# Puzzle_Serial_Bluetooth_v0_9b.net
KiCad netlist of a schematic drawn in EAGLE
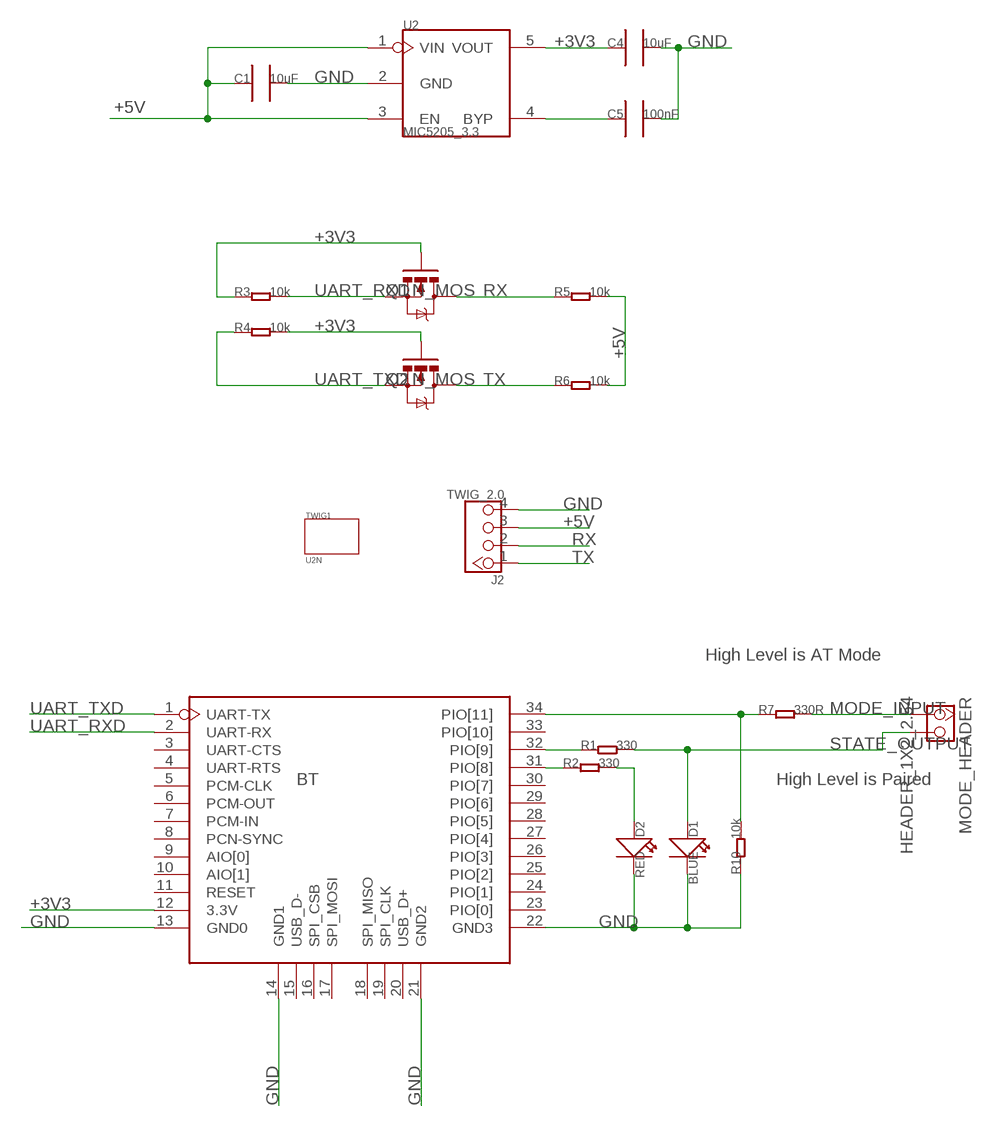
[diagram p0: schematic, sheet 1]

(export (version "E")
  (design (tool "Eeschema 10.0.6"))
  (components
    (comp (ref "BT")
      (value "SERIAL_BLUETEETHSMT")
      (footprint "eagle-import:SERIAL_BLUETEETH")
      (libsource (lib "eagle-import") (part "SERIAL_BLUETEETHSMT"))
    )
    (comp (ref "C1")
      (value "10uF")
      (footprint "eagle-import:0805_S")
      (libsource (lib "eagle-import") (part "C0805_S"))
    )
    (comp (ref "C4")
      (value "10uF")
      (footprint "eagle-import:0805_S")
      (libsource (lib "eagle-import") (part "C0805_S"))
    )
    (comp (ref "C5")
      (value "100nF")
      (footprint "eagle-import:0603_S")
      (libsource (lib "eagle-import") (part "C0603_S"))
    )
    (comp (ref "D1")
      (value "BLUE")
      (footprint "eagle-import:LED0603")
      (libsource (lib "eagle-import") (part "LED0603_DD"))
    )
    (comp (ref "D2")
      (value "RED")
      (footprint "eagle-import:LED0603")
      (libsource (lib "eagle-import") (part "LED0603_DD"))
    )
    (comp (ref "J2")
      (value "TWIG_2.0")
      (footprint "eagle-import:2.0_1X4")
      (libsource (lib "eagle-import") (part "TWIG_2.0"))
    )
    (comp (ref "MODE_HEADER")
      (value "HEADER_1X2_2.54")
      (footprint "eagle-import:CK_1_2")
      (libsource (lib "eagle-import") (part "HEADER_1X2_2.54"))
    )
    (comp (ref "Q1")
      (value "N_MOS")
      (footprint "eagle-import:SOT23")
      (libsource (lib "eagle-import") (part "N_MOS"))
    )
    (comp (ref "Q2")
      (value "N_MOS")
      (footprint "eagle-import:SOT23")
      (libsource (lib "eagle-import") (part "N_MOS"))
    )
    (comp (ref "R1")
      (value "330")
      (footprint "eagle-import:0603")
      (libsource (lib "eagle-import") (part "R0603"))
    )
    (comp (ref "R2")
      (value "330")
      (footprint "eagle-import:0603")
      (libsource (lib "eagle-import") (part "R0603"))
    )
    (comp (ref "R3")
      (value "10k")
      (footprint "eagle-import:0603_S")
      (libsource (lib "eagle-import") (part "R0603_S"))
    )
    (comp (ref "R4")
      (value "10k")
      (footprint "eagle-import:0603_S")
      (libsource (lib "eagle-import") (part "R0603_S"))
    )
    (comp (ref "R5")
      (value "10k")
      (footprint "eagle-import:0603_S")
      (libsource (lib "eagle-import") (part "R0603_S"))
    )
    (comp (ref "R6")
      (value "10k")
      (footprint "eagle-import:0603_S")
      (libsource (lib "eagle-import") (part "R0603_S"))
    )
    (comp (ref "R7")
      (value "330R")
      (footprint "eagle-import:0603_S")
      (libsource (lib "eagle-import") (part "R0603_S"))
    )
    (comp (ref "R10")
      (value "10k")
      (footprint "eagle-import:0603_S")
      (libsource (lib "eagle-import") (part "R0603_S"))
    )
    (comp (ref "TWIG1")
      (value "U2N")
      (footprint "eagle-import:U2N")
      (libsource (lib "eagle-import") (part "U2N"))
    )
    (comp (ref "U2")
      (value "MIC5205_3.3")
      (footprint "eagle-import:SOT23-5")
      (libsource (lib "eagle-import") (part "MIC5025_X.X"))
    )
  )
  (nets
    (net (code "1") (name "/+3V3") (class "Default")
      (node (ref "BT") (pin "12") (pinfunction "3.3V_12") (pintype "bidirectional"))
      (node (ref "C4") (pin "1") (pinfunction "1_1") (pintype "bidirectional"))
      (node (ref "Q1") (pin "1") (pinfunction "G_1") (pintype "passive"))
      (node (ref "Q2") (pin "1") (pinfunction "G_1") (pintype "passive"))
      (node (ref "R3") (pin "1") (pinfunction "1_1") (pintype "bidirectional"))
      (node (ref "R4") (pin "2") (pinfunction "2_2") (pintype "bidirectional"))
      (node (ref "U2") (pin "5") (pinfunction "VOUT_5") (pintype "bidirectional"))
    )
    (net (code "2") (name "/+5V") (class "Default")
      (node (ref "C1") (pin "1") (pinfunction "1_1") (pintype "bidirectional"))
      (node (ref "J2") (pin "3") (pinfunction "3_3") (pintype "bidirectional"))
      (node (ref "R5") (pin "2") (pinfunction "2_2") (pintype "bidirectional"))
      (node (ref "R6") (pin "2") (pinfunction "2_2") (pintype "bidirectional"))
      (node (ref "U2") (pin "1") (pinfunction "VIN_1") (pintype "bidirectional"))
      (node (ref "U2") (pin "3") (pinfunction "EN_3") (pintype "bidirectional"))
    )
    (net (code "3") (name "/GND") (class "Default")
      (node (ref "BT") (pin "13") (pinfunction "GND0_13") (pintype "bidirectional"))
      (node (ref "BT") (pin "14") (pinfunction "GND1_14") (pintype "bidirectional"))
      (node (ref "BT") (pin "21") (pinfunction "GND2_21") (pintype "bidirectional"))
      (node (ref "BT") (pin "22") (pinfunction "GND3_22") (pintype "bidirectional"))
      (node (ref "C1") (pin "2") (pinfunction "2_2") (pintype "bidirectional"))
      (node (ref "C4") (pin "2") (pinfunction "2_2") (pintype "bidirectional"))
      (node (ref "C5") (pin "2") (pinfunction "2_2") (pintype "bidirectional"))
      (node (ref "D1") (pin "2") (pinfunction "-_2") (pintype "bidirectional"))
      (node (ref "D2") (pin "2") (pinfunction "-_2") (pintype "bidirectional"))
      (node (ref "J2") (pin "4") (pinfunction "4_4") (pintype "bidirectional"))
      (node (ref "R10") (pin "1") (pinfunction "1_1") (pintype "bidirectional"))
      (node (ref "U2") (pin "2") (pinfunction "GND_2") (pintype "bidirectional"))
    )
    (net (code "4") (name "/MODE_INPUT") (class "Default")
      (node (ref "MODE_HEADER") (pin "1") (pinfunction "1_1") (pintype "bidirectional"))
      (node (ref "R7") (pin "2") (pinfunction "2_2") (pintype "bidirectional"))
    )
    (net (code "5") (name "/RX") (class "Default")
      (node (ref "J2") (pin "2") (pinfunction "2_2") (pintype "bidirectional"))
      (node (ref "Q1") (pin "3") (pinfunction "D_3") (pintype "passive"))
      (node (ref "R5") (pin "1") (pinfunction "1_1") (pintype "bidirectional"))
    )
    (net (code "6") (name "/STATE_OUTPUT") (class "Default")
      (node (ref "D1") (pin "1") (pinfunction "+_1") (pintype "bidirectional"))
      (node (ref "MODE_HEADER") (pin "2") (pinfunction "2_2") (pintype "bidirectional"))
      (node (ref "R1") (pin "2") (pinfunction "2_2") (pintype "bidirectional"))
    )
    (net (code "7") (name "/TX") (class "Default")
      (node (ref "J2") (pin "1") (pinfunction "1_1") (pintype "bidirectional"))
      (node (ref "Q2") (pin "3") (pinfunction "D_3") (pintype "passive"))
      (node (ref "R6") (pin "1") (pinfunction "1_1") (pintype "bidirectional"))
    )
    (net (code "8") (name "/UART_RXD") (class "Default")
      (node (ref "BT") (pin "2") (pinfunction "UART-RX_2") (pintype "bidirectional"))
      (node (ref "Q1") (pin "2") (pinfunction "S_2") (pintype "passive"))
      (node (ref "R3") (pin "2") (pinfunction "2_2") (pintype "bidirectional"))
    )
    (net (code "9") (name "/UART_TXD") (class "Default")
      (node (ref "BT") (pin "1") (pinfunction "UART-TX_1") (pintype "bidirectional"))
      (node (ref "Q2") (pin "2") (pinfunction "S_2") (pintype "passive"))
      (node (ref "R4") (pin "1") (pinfunction "1_1") (pintype "bidirectional"))
    )
    (net (code "10") (name "Net-(BT-PIO[8])") (class "Default")
      (node (ref "BT") (pin "31") (pinfunction "PIO[8]_31") (pintype "bidirectional"))
      (node (ref "R2") (pin "1") (pinfunction "1_1") (pintype "bidirectional"))
    )
    (net (code "11") (name "Net-(BT-PIO[9])") (class "Default")
      (node (ref "BT") (pin "32") (pinfunction "PIO[9]_32") (pintype "bidirectional"))
      (node (ref "R1") (pin "1") (pinfunction "1_1") (pintype "bidirectional"))
    )
    (net (code "12") (name "Net-(BT-PIO[11])") (class "Default")
      (node (ref "BT") (pin "34") (pinfunction "PIO[11]_34") (pintype "bidirectional"))
      (node (ref "R10") (pin "2") (pinfunction "2_2") (pintype "bidirectional"))
      (node (ref "R7") (pin "1") (pinfunction "1_1") (pintype "bidirectional"))
    )
    (net (code "13") (name "Net-(D2-+)") (class "Default")
      (node (ref "D2") (pin "1") (pinfunction "+_1") (pintype "bidirectional"))
      (node (ref "R2") (pin "2") (pinfunction "2_2") (pintype "bidirectional"))
    )
    (net (code "14") (name "Net-(U2-BYP)") (class "Default")
      (node (ref "C5") (pin "1") (pinfunction "1_1") (pintype "bidirectional"))
      (node (ref "U2") (pin "4") (pinfunction "BYP_4") (pintype "bidirectional"))
    )
    (net (code "15") (name "unconnected-(BT-AIO[0]-Pad9)") (class "Default")
      (node (ref "BT") (pin "9") (pinfunction "AIO[0]_9") (pintype "bidirectional"))
    )
    (net (code "16") (name "unconnected-(BT-AIO[1]-Pad10)") (class "Default")
      (node (ref "BT") (pin "10") (pinfunction "AIO[1]_10") (pintype "bidirectional"))
    )
    (net (code "17") (name "unconnected-(BT-PCM-CLK-Pad5)") (class "Default")
      (node (ref "BT") (pin "5") (pinfunction "PCM-CLK_5") (pintype "bidirectional"))
    )
    (net (code "18") (name "unconnected-(BT-PCM-IN-Pad7)") (class "Default")
      (node (ref "BT") (pin "7") (pinfunction "PCM-IN_7") (pintype "bidirectional"))
    )
    (net (code "19") (name "unconnected-(BT-PCM-OUT-Pad6)") (class "Default")
      (node (ref "BT") (pin "6") (pinfunction "PCM-OUT_6") (pintype "bidirectional"))
    )
    (net (code "20") (name "unconnected-(BT-PCN-SYNC-Pad8)") (class "Default")
      (node (ref "BT") (pin "8") (pinfunction "PCN-SYNC_8") (pintype "bidirectional"))
    )
    (net (code "21") (name "unconnected-(BT-PIO[0]-Pad23)") (class "Default")
      (node (ref "BT") (pin "23") (pinfunction "PIO[0]_23") (pintype "bidirectional"))
    )
    (net (code "22") (name "unconnected-(BT-PIO[1]-Pad24)") (class "Default")
      (node (ref "BT") (pin "24") (pinfunction "PIO[1]_24") (pintype "bidirectional"))
    )
    (net (code "23") (name "unconnected-(BT-PIO[2]-Pad25)") (class "Default")
      (node (ref "BT") (pin "25") (pinfunction "PIO[2]_25") (pintype "bidirectional"))
    )
    (net (code "24") (name "unconnected-(BT-PIO[3]-Pad26)") (class "Default")
      (node (ref "BT") (pin "26") (pinfunction "PIO[3]_26") (pintype "bidirectional"))
    )
    (net (code "25") (name "unconnected-(BT-PIO[4]-Pad27)") (class "Default")
      (node (ref "BT") (pin "27") (pinfunction "PIO[4]_27") (pintype "bidirectional"))
    )
    (net (code "26") (name "unconnected-(BT-PIO[5]-Pad28)") (class "Default")
      (node (ref "BT") (pin "28") (pinfunction "PIO[5]_28") (pintype "bidirectional"))
    )
    (net (code "27") (name "unconnected-(BT-PIO[6]-Pad29)") (class "Default")
      (node (ref "BT") (pin "29") (pinfunction "PIO[6]_29") (pintype "bidirectional"))
    )
    (net (code "28") (name "unconnected-(BT-PIO[7]-Pad30)") (class "Default")
      (node (ref "BT") (pin "30") (pinfunction "PIO[7]_30") (pintype "bidirectional"))
    )
    (net (code "29") (name "unconnected-(BT-PIO[10]-Pad33)") (class "Default")
      (node (ref "BT") (pin "33") (pinfunction "PIO[10]_33") (pintype "bidirectional"))
    )
    (net (code "30") (name "unconnected-(BT-RESET-Pad11)") (class "Default")
      (node (ref "BT") (pin "11") (pinfunction "RESET_11") (pintype "bidirectional"))
    )
    (net (code "31") (name "unconnected-(BT-SPI_CLK-Pad19)") (class "Default")
      (node (ref "BT") (pin "19") (pinfunction "SPI_CLK_19") (pintype "bidirectional"))
    )
    (net (code "32") (name "unconnected-(BT-SPI_CSB-Pad16)") (class "Default")
      (node (ref "BT") (pin "16") (pinfunction "SPI_CSB_16") (pintype "bidirectional"))
    )
    (net (code "33") (name "unconnected-(BT-SPI_MISO-Pad18)") (class "Default")
      (node (ref "BT") (pin "18") (pinfunction "SPI_MISO_18") (pintype "bidirectional"))
    )
    (net (code "34") (name "unconnected-(BT-SPI_MOSI-Pad17)") (class "Default")
      (node (ref "BT") (pin "17") (pinfunction "SPI_MOSI_17") (pintype "bidirectional"))
    )
    (net (code "35") (name "unconnected-(BT-UART-CTS-Pad3)") (class "Default")
      (node (ref "BT") (pin "3") (pinfunction "UART-CTS_3") (pintype "bidirectional"))
    )
    (net (code "36") (name "unconnected-(BT-UART-RTS-Pad4)") (class "Default")
      (node (ref "BT") (pin "4") (pinfunction "UART-RTS_4") (pintype "bidirectional"))
    )
    (net (code "37") (name "unconnected-(BT-USB_D+-Pad20)") (class "Default")
      (node (ref "BT") (pin "20") (pinfunction "USB_D+_20") (pintype "bidirectional"))
    )
    (net (code "38") (name "unconnected-(BT-USB_D--Pad15)") (class "Default")
      (node (ref "BT") (pin "15") (pinfunction "USB_D-_15") (pintype "bidirectional"))
    )
  )
)
